# Memory.net
KiCad netlist of a schematic drawn in Altium Designer
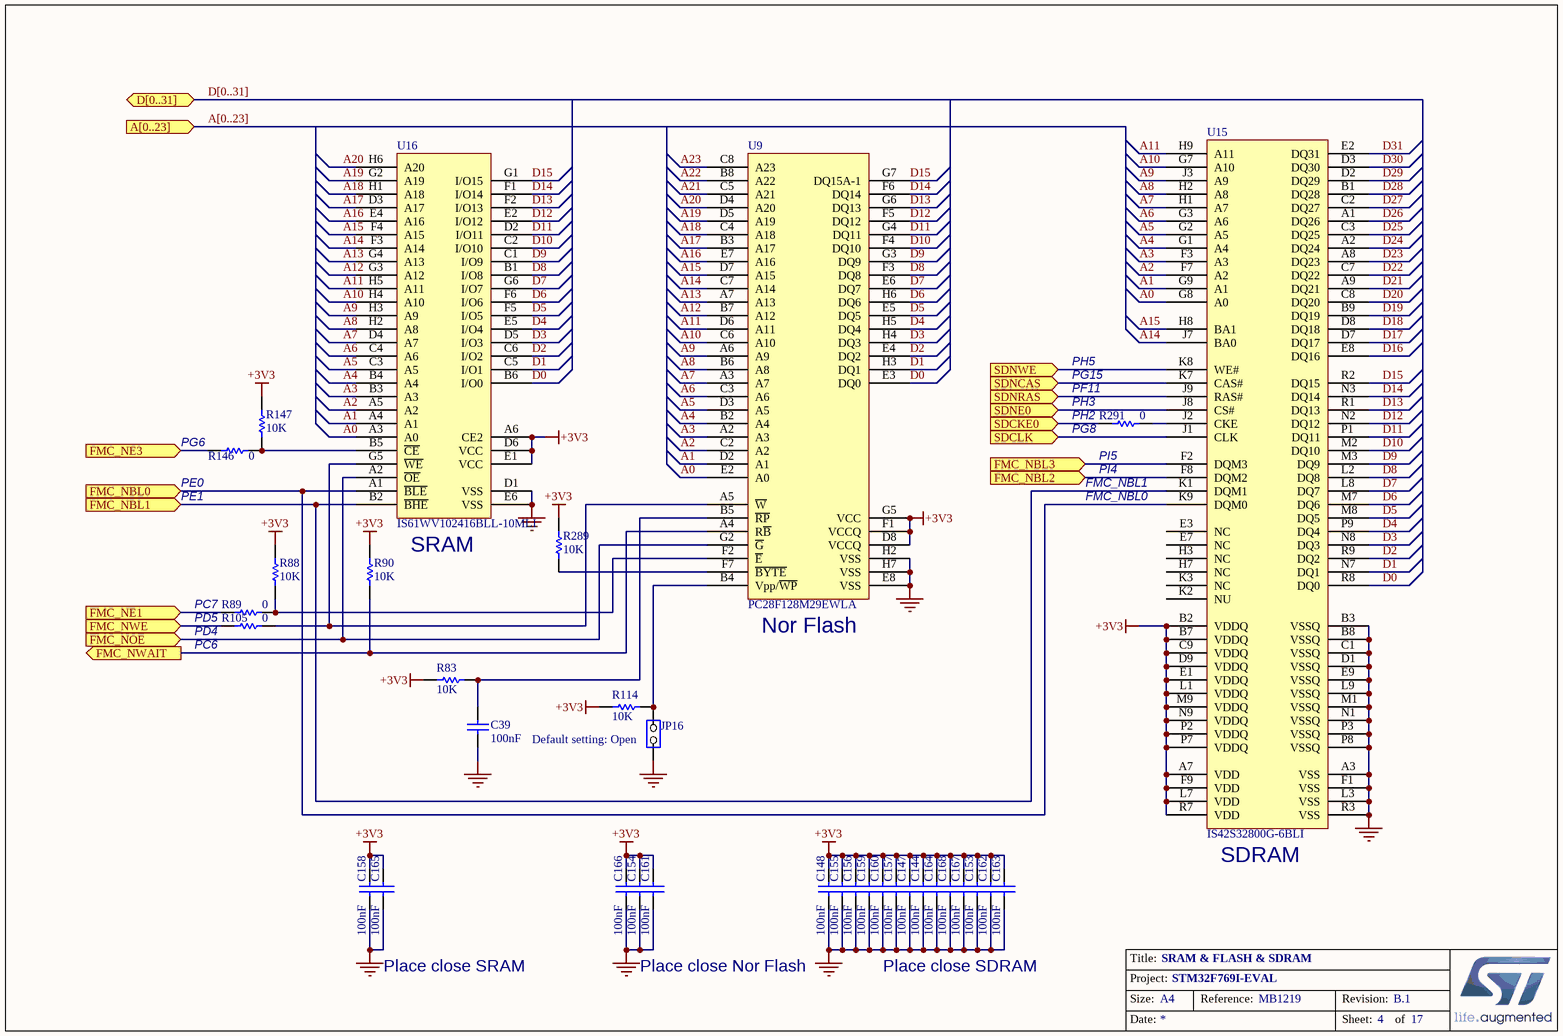
[diagram p0: Memory.SchDoc]

(export (version "E")
  (design (tool "Eeschema 10.0.6"))
  (components
    (comp (ref "C39")
      (value "100nF")
      (footprint "0603C")
      (description "Capacitor")
      (fields (field (name "PUBLISHER") "Altium Limited"))
      (libsource (lib "Miscellaneous Devices") (part "Cap"))
    )
    (comp (ref "C144")
      (value "100nF")
      (footprint "0603C")
      (description "Capacitor")
      (fields (field (name "PUBLISHER") "Altium Limited"))
      (libsource (lib "Miscellaneous Devices") (part "Cap"))
    )
    (comp (ref "C147")
      (value "100nF")
      (footprint "0603C")
      (description "Capacitor")
      (fields (field (name "PUBLISHER") "Altium Limited"))
      (libsource (lib "Miscellaneous Devices") (part "Cap"))
    )
    (comp (ref "C148")
      (value "100nF")
      (footprint "0603C")
      (description "Capacitor")
      (fields (field (name "PUBLISHER") "Altium Limited"))
      (libsource (lib "Miscellaneous Devices") (part "Cap"))
    )
    (comp (ref "C153")
      (value "100nF")
      (footprint "0603C")
      (description "Capacitor")
      (fields (field (name "PUBLISHER") "Altium Limited"))
      (libsource (lib "Miscellaneous Devices") (part "Cap"))
    )
    (comp (ref "C154")
      (value "100nF")
      (footprint "0603C")
      (description "Capacitor")
      (fields (field (name "PUBLISHER") "Altium Limited"))
      (libsource (lib "Miscellaneous Devices") (part "Cap"))
    )
    (comp (ref "C155")
      (value "100nF")
      (footprint "0603C")
      (description "Capacitor")
      (fields (field (name "PUBLISHER") "Altium Limited"))
      (libsource (lib "Miscellaneous Devices") (part "Cap"))
    )
    (comp (ref "C156")
      (value "100nF")
      (footprint "0603C")
      (description "Capacitor")
      (fields (field (name "PUBLISHER") "Altium Limited"))
      (libsource (lib "Miscellaneous Devices") (part "Cap"))
    )
    (comp (ref "C157")
      (value "100nF")
      (footprint "0603C")
      (description "Capacitor")
      (fields (field (name "PUBLISHER") "Altium Limited"))
      (libsource (lib "Miscellaneous Devices") (part "Cap"))
    )
    (comp (ref "C158")
      (value "100nF")
      (footprint "0603C")
      (description "Capacitor")
      (fields (field (name "PUBLISHER") "Altium Limited"))
      (libsource (lib "Miscellaneous Devices") (part "Cap"))
    )
    (comp (ref "C159")
      (value "100nF")
      (footprint "0603C")
      (description "Capacitor")
      (fields (field (name "PUBLISHER") "Altium Limited"))
      (libsource (lib "Miscellaneous Devices") (part "Cap"))
    )
    (comp (ref "C160")
      (value "100nF")
      (footprint "0603C")
      (description "Capacitor")
      (fields (field (name "PUBLISHER") "Altium Limited"))
      (libsource (lib "Miscellaneous Devices") (part "Cap"))
    )
    (comp (ref "C161")
      (value "100nF")
      (footprint "0603C")
      (description "Capacitor")
      (fields (field (name "PUBLISHER") "Altium Limited"))
      (libsource (lib "Miscellaneous Devices") (part "Cap"))
    )
    (comp (ref "C162")
      (value "100nF")
      (footprint "0603C")
      (description "Capacitor")
      (fields (field (name "PUBLISHER") "Altium Limited"))
      (libsource (lib "Miscellaneous Devices") (part "Cap"))
    )
    (comp (ref "C163")
      (value "100nF")
      (footprint "0603C")
      (description "Capacitor")
      (fields (field (name "PUBLISHER") "Altium Limited"))
      (libsource (lib "Miscellaneous Devices") (part "Cap"))
    )
    (comp (ref "C164")
      (value "100nF")
      (footprint "0603C")
      (description "Capacitor")
      (fields (field (name "PUBLISHER") "Altium Limited"))
      (libsource (lib "Miscellaneous Devices") (part "Cap"))
    )
    (comp (ref "C165")
      (value "100nF")
      (footprint "0603C")
      (description "Capacitor")
      (fields (field (name "PUBLISHER") "Altium Limited"))
      (libsource (lib "Miscellaneous Devices") (part "Cap"))
    )
    (comp (ref "C166")
      (value "100nF")
      (footprint "0603C")
      (description "Capacitor")
      (fields (field (name "PUBLISHER") "Altium Limited"))
      (libsource (lib "Miscellaneous Devices") (part "Cap"))
    )
    (comp (ref "C167")
      (value "100nF")
      (footprint "0603C")
      (description "Capacitor")
      (fields (field (name "PUBLISHER") "Altium Limited"))
      (libsource (lib "Miscellaneous Devices") (part "Cap"))
    )
    (comp (ref "C168")
      (value "100nF")
      (footprint "0603C")
      (description "Capacitor")
      (fields (field (name "PUBLISHER") "Altium Limited"))
      (libsource (lib "Miscellaneous Devices") (part "Cap"))
    )
    (comp (ref "JP16") (value "~") (footprint "SIP2") (libsource (lib "*") (part "JP2")))
    (comp (ref "R83")
      (value "10K")
      (footprint "0603R")
      (description "Resistor")
      (fields (field (name "PUBLISHER") "Altium Limited"))
      (libsource (lib "Miscellaneous Devices") (part "Res1"))
    )
    (comp (ref "R88")
      (value "10K")
      (footprint "0603R")
      (description "Resistor")
      (fields (field (name "PUBLISHER") "Altium Limited"))
      (libsource (lib "Miscellaneous Devices") (part "Res1"))
    )
    (comp (ref "R89")
      (value "0")
      (footprint "0603R")
      (description "Resistor")
      (fields (field (name "PUBLISHER") "Altium Limited"))
      (libsource (lib "Miscellaneous Devices") (part "Res1"))
    )
    (comp (ref "R90")
      (value "10K")
      (footprint "0603R")
      (description "Resistor")
      (fields (field (name "PUBLISHER") "Altium Limited"))
      (libsource (lib "Miscellaneous Devices") (part "Res1"))
    )
    (comp (ref "R105")
      (value "0")
      (footprint "0603R")
      (description "Resistor")
      (fields (field (name "PUBLISHER") "Altium Limited"))
      (libsource (lib "Miscellaneous Devices") (part "Res1"))
    )
    (comp (ref "R114")
      (value "10K")
      (footprint "0603R")
      (description "Resistor")
      (fields (field (name "PUBLISHER") "Altium Limited"))
      (libsource (lib "Miscellaneous Devices") (part "Res1"))
    )
    (comp (ref "R146")
      (value "0")
      (footprint "0603R")
      (description "Resistor")
      (fields (field (name "PUBLISHER") "Altium Limited"))
      (libsource (lib "Miscellaneous Devices") (part "Res1"))
    )
    (comp (ref "R147")
      (value "10K")
      (footprint "0603R")
      (description "Resistor")
      (fields (field (name "PUBLISHER") "Altium Limited"))
      (libsource (lib "Miscellaneous Devices") (part "Res1"))
    )
    (comp (ref "R289")
      (value "10K")
      (footprint "0603R")
      (description "Resistor")
      (fields (field (name "PUBLISHER") "Altium Limited"))
      (libsource (lib "Miscellaneous Devices") (part "Res1"))
    )
    (comp (ref "R291")
      (value "0")
      (footprint "0603R")
      (description "Resistor")
      (fields (field (name "PUBLISHER") "Altium Limited"))
      (libsource (lib "Miscellaneous Devices") (part "Res1"))
    )
    (comp (ref "U9")
      (value "PC28F128M29EWLA")
      (footprint "FBGA64_1_11X13")
      (libsource (lib "MB964") (part "M29W128FL70ZA6E"))
    )
    (comp (ref "U15")
      (value "IS42S32800G-6BLI")
      (footprint "FBGA90_0R8_8X13")
      (libsource (lib "mb1045") (part "MT48LC4M32B2B5"))
    )
    (comp (ref "U16")
      (value "IS61WV102416BLL-10MLI")
      (footprint "BGA48_0R75_9X11")
      (libsource (lib "MB901") (part "IS61WV102416BLL-10MLI"))
    )
  )
  (nets
    (net (code "1") (name "+3V3") (class "Default")
      (node (ref "C144") (pin "1") (pinfunction "1_1") (pintype "passive"))
      (node (ref "C147") (pin "1") (pinfunction "1_1") (pintype "passive"))
      (node (ref "C148") (pin "1") (pinfunction "1_1") (pintype "passive"))
      (node (ref "C153") (pin "1") (pinfunction "1_1") (pintype "passive"))
      (node (ref "C154") (pin "1") (pinfunction "1_1") (pintype "passive"))
      (node (ref "C155") (pin "1") (pinfunction "1_1") (pintype "passive"))
      (node (ref "C156") (pin "1") (pinfunction "1_1") (pintype "passive"))
      (node (ref "C157") (pin "1") (pinfunction "1_1") (pintype "passive"))
      (node (ref "C158") (pin "1") (pinfunction "1_1") (pintype "passive"))
      (node (ref "C159") (pin "1") (pinfunction "1_1") (pintype "passive"))
      (node (ref "C160") (pin "1") (pinfunction "1_1") (pintype "passive"))
      (node (ref "C161") (pin "1") (pinfunction "1_1") (pintype "passive"))
      (node (ref "C162") (pin "1") (pinfunction "1_1") (pintype "passive"))
      (node (ref "C163") (pin "1") (pinfunction "1_1") (pintype "passive"))
      (node (ref "C164") (pin "1") (pinfunction "1_1") (pintype "passive"))
      (node (ref "C165") (pin "1") (pinfunction "1_1") (pintype "passive"))
      (node (ref "C166") (pin "1") (pinfunction "1_1") (pintype "passive"))
      (node (ref "C167") (pin "1") (pinfunction "1_1") (pintype "passive"))
      (node (ref "C168") (pin "1") (pinfunction "1_1") (pintype "passive"))
      (node (ref "R114") (pin "2") (pinfunction "2_2") (pintype "passive"))
      (node (ref "R147") (pin "2") (pinfunction "2_2") (pintype "passive"))
      (node (ref "R289") (pin "2") (pinfunction "2_2") (pintype "passive"))
      (node (ref "R83") (pin "1") (pinfunction "1_1") (pintype "passive"))
      (node (ref "R88") (pin "2") (pinfunction "2_2") (pintype "passive"))
      (node (ref "R90") (pin "2") (pinfunction "2_2") (pintype "passive"))
      (node (ref "U15") (pin "A7") (pinfunction "VDD_A7") (pintype "passive"))
      (node (ref "U15") (pin "B2") (pinfunction "VDDQ_B2") (pintype "passive"))
      (node (ref "U15") (pin "B7") (pinfunction "VDDQ_B7") (pintype "passive"))
      (node (ref "U15") (pin "C9") (pinfunction "VDDQ_C9") (pintype "passive"))
      (node (ref "U15") (pin "D9") (pinfunction "VDDQ_D9") (pintype "passive"))
      (node (ref "U15") (pin "E1") (pinfunction "VDDQ_E1") (pintype "passive"))
      (node (ref "U15") (pin "F9") (pinfunction "VDD_F9") (pintype "passive"))
      (node (ref "U15") (pin "L1") (pinfunction "VDDQ_L1") (pintype "passive"))
      (node (ref "U15") (pin "L7") (pinfunction "VDD_L7") (pintype "passive"))
      (node (ref "U15") (pin "M9") (pinfunction "VDDQ_M9") (pintype "passive"))
      (node (ref "U15") (pin "N9") (pinfunction "VDDQ_N9") (pintype "passive"))
      (node (ref "U15") (pin "P2") (pinfunction "VDDQ_P2") (pintype "passive"))
      (node (ref "U15") (pin "P7") (pinfunction "VDDQ_P7") (pintype "passive"))
      (node (ref "U15") (pin "R7") (pinfunction "VDD_R7") (pintype "passive"))
      (node (ref "U16") (pin "A6") (pinfunction "CE2_A6") (pintype "passive"))
      (node (ref "U16") (pin "D6") (pinfunction "VCC_D6") (pintype "passive"))
      (node (ref "U16") (pin "E1") (pinfunction "VCC_E1") (pintype "passive"))
      (node (ref "U9") (pin "D8") (pinfunction "VCCQ_D8") (pintype "passive"))
      (node (ref "U9") (pin "F1") (pinfunction "VCCQ_F1") (pintype "passive"))
      (node (ref "U9") (pin "G5") (pinfunction "VCC_G5") (pintype "passive"))
    )
    (net (code "2") (name "/A0") (class "Default")
      (node (ref "U15") (pin "G8") (pinfunction "A0_G8") (pintype "passive"))
      (node (ref "U16") (pin "A3") (pinfunction "A0_A3") (pintype "passive"))
      (node (ref "U9") (pin "E2") (pinfunction "A0_E2") (pintype "passive"))
    )
    (net (code "3") (name "/A1") (class "Default")
      (node (ref "U15") (pin "G9") (pinfunction "A1_G9") (pintype "passive"))
      (node (ref "U16") (pin "A4") (pinfunction "A1_A4") (pintype "passive"))
      (node (ref "U9") (pin "D2") (pinfunction "A1_D2") (pintype "passive"))
    )
    (net (code "4") (name "/A2") (class "Default")
      (node (ref "U15") (pin "F7") (pinfunction "A2_F7") (pintype "passive"))
      (node (ref "U16") (pin "A5") (pinfunction "A2_A5") (pintype "passive"))
      (node (ref "U9") (pin "C2") (pinfunction "A2_C2") (pintype "passive"))
    )
    (net (code "5") (name "/A3") (class "Default")
      (node (ref "U15") (pin "F3") (pinfunction "A3_F3") (pintype "passive"))
      (node (ref "U16") (pin "B3") (pinfunction "A3_B3") (pintype "passive"))
      (node (ref "U9") (pin "A2") (pinfunction "A3_A2") (pintype "passive"))
    )
    (net (code "6") (name "/A4") (class "Default")
      (node (ref "U15") (pin "G1") (pinfunction "A4_G1") (pintype "passive"))
      (node (ref "U16") (pin "B4") (pinfunction "A4_B4") (pintype "passive"))
      (node (ref "U9") (pin "B2") (pinfunction "A4_B2") (pintype "passive"))
    )
    (net (code "7") (name "/A5") (class "Default")
      (node (ref "U15") (pin "G2") (pinfunction "A5_G2") (pintype "passive"))
      (node (ref "U16") (pin "C3") (pinfunction "A5_C3") (pintype "passive"))
      (node (ref "U9") (pin "D3") (pinfunction "A5_D3") (pintype "passive"))
    )
    (net (code "8") (name "/A6") (class "Default")
      (node (ref "U15") (pin "G3") (pinfunction "A6_G3") (pintype "passive"))
      (node (ref "U16") (pin "C4") (pinfunction "A6_C4") (pintype "passive"))
      (node (ref "U9") (pin "C3") (pinfunction "A6_C3") (pintype "passive"))
    )
    (net (code "9") (name "/A7") (class "Default")
      (node (ref "U15") (pin "H1") (pinfunction "A7_H1") (pintype "passive"))
      (node (ref "U16") (pin "D4") (pinfunction "A7_D4") (pintype "passive"))
      (node (ref "U9") (pin "A3") (pinfunction "A7_A3") (pintype "passive"))
    )
    (net (code "10") (name "/A8") (class "Default")
      (node (ref "U15") (pin "H2") (pinfunction "A8_H2") (pintype "passive"))
      (node (ref "U16") (pin "H2") (pinfunction "A8_H2") (pintype "passive"))
      (node (ref "U9") (pin "B6") (pinfunction "A8_B6") (pintype "passive"))
    )
    (net (code "11") (name "/A9") (class "Default")
      (node (ref "U15") (pin "J3") (pinfunction "A9_J3") (pintype "passive"))
      (node (ref "U16") (pin "H3") (pinfunction "A9_H3") (pintype "passive"))
      (node (ref "U9") (pin "A6") (pinfunction "A9_A6") (pintype "passive"))
    )
    (net (code "12") (name "/A10") (class "Default")
      (node (ref "U15") (pin "G7") (pinfunction "A10_G7") (pintype "passive"))
      (node (ref "U16") (pin "H4") (pinfunction "A10_H4") (pintype "passive"))
      (node (ref "U9") (pin "C6") (pinfunction "A10_C6") (pintype "passive"))
    )
    (net (code "13") (name "/A11") (class "Default")
      (node (ref "U15") (pin "H9") (pinfunction "A11_H9") (pintype "passive"))
      (node (ref "U16") (pin "H5") (pinfunction "A11_H5") (pintype "passive"))
      (node (ref "U9") (pin "D6") (pinfunction "A11_D6") (pintype "passive"))
    )
    (net (code "14") (name "/A12") (class "Default")
      (node (ref "U16") (pin "G3") (pinfunction "A12_G3") (pintype "passive"))
      (node (ref "U9") (pin "B7") (pinfunction "A12_B7") (pintype "passive"))
    )
    (net (code "15") (name "/A13") (class "Default")
      (node (ref "U16") (pin "G4") (pinfunction "A13_G4") (pintype "passive"))
      (node (ref "U9") (pin "A7") (pinfunction "A13_A7") (pintype "passive"))
    )
    (net (code "16") (name "/A14") (class "Default")
      (node (ref "U15") (pin "J7") (pinfunction "BA0_J7") (pintype "passive"))
      (node (ref "U16") (pin "F3") (pinfunction "A14_F3") (pintype "passive"))
      (node (ref "U9") (pin "C7") (pinfunction "A14_C7") (pintype "passive"))
    )
    (net (code "17") (name "/A15") (class "Default")
      (node (ref "U15") (pin "H8") (pinfunction "BA1_H8") (pintype "passive"))
      (node (ref "U16") (pin "F4") (pinfunction "A15_F4") (pintype "passive"))
      (node (ref "U9") (pin "D7") (pinfunction "A15_D7") (pintype "passive"))
    )
    (net (code "18") (name "/A16") (class "Default")
      (node (ref "U16") (pin "E4") (pinfunction "A16_E4") (pintype "passive"))
      (node (ref "U9") (pin "E7") (pinfunction "A16_E7") (pintype "passive"))
    )
    (net (code "19") (name "/A17") (class "Default")
      (node (ref "U16") (pin "D3") (pinfunction "A17_D3") (pintype "passive"))
      (node (ref "U9") (pin "B3") (pinfunction "A17_B3") (pintype "passive"))
    )
    (net (code "20") (name "/A18") (class "Default")
      (node (ref "U16") (pin "H1") (pinfunction "A18_H1") (pintype "passive"))
      (node (ref "U9") (pin "C4") (pinfunction "A18_C4") (pintype "passive"))
    )
    (net (code "21") (name "/A19") (class "Default")
      (node (ref "U16") (pin "G2") (pinfunction "A19_G2") (pintype "passive"))
      (node (ref "U9") (pin "D5") (pinfunction "A19_D5") (pintype "passive"))
    )
    (net (code "22") (name "/A20") (class "Default")
      (node (ref "U16") (pin "H6") (pinfunction "A20_H6") (pintype "passive"))
      (node (ref "U9") (pin "D4") (pinfunction "A20_D4") (pintype "passive"))
    )
    (net (code "23") (name "/A21") (class "Default")
      (node (ref "U9") (pin "C5") (pinfunction "A21_C5") (pintype "passive"))
    )
    (net (code "24") (name "/A22") (class "Default")
      (node (ref "U9") (pin "B8") (pinfunction "A22_B8") (pintype "passive"))
    )
    (net (code "25") (name "/A23") (class "Default")
      (node (ref "U9") (pin "C8") (pinfunction "A23_C8") (pintype "passive"))
    )
    (net (code "27") (name "/D0") (class "Default")
      (node (ref "U15") (pin "R8") (pinfunction "DQ0_R8") (pintype "passive"))
      (node (ref "U16") (pin "B6") (pinfunction "I/O0_B6") (pintype "passive"))
      (node (ref "U9") (pin "E3") (pinfunction "DQ0_E3") (pintype "passive"))
    )
    (net (code "28") (name "/D1") (class "Default")
      (node (ref "U15") (pin "N7") (pinfunction "DQ1_N7") (pintype "passive"))
      (node (ref "U16") (pin "C5") (pinfunction "I/O1_C5") (pintype "passive"))
      (node (ref "U9") (pin "H3") (pinfunction "DQ1_H3") (pintype "passive"))
    )
    (net (code "29") (name "/D2") (class "Default")
      (node (ref "U15") (pin "R9") (pinfunction "DQ2_R9") (pintype "passive"))
      (node (ref "U16") (pin "C6") (pinfunction "I/O2_C6") (pintype "passive"))
      (node (ref "U9") (pin "E4") (pinfunction "DQ2_E4") (pintype "passive"))
    )
    (net (code "30") (name "/D3") (class "Default")
      (node (ref "U15") (pin "N8") (pinfunction "DQ3_N8") (pintype "passive"))
      (node (ref "U16") (pin "D5") (pinfunction "I/O3_D5") (pintype "passive"))
      (node (ref "U9") (pin "H4") (pinfunction "DQ3_H4") (pintype "passive"))
    )
    (net (code "31") (name "/D4") (class "Default")
      (node (ref "U15") (pin "P9") (pinfunction "DQ4_P9") (pintype "passive"))
      (node (ref "U16") (pin "E5") (pinfunction "I/O4_E5") (pintype "passive"))
      (node (ref "U9") (pin "H5") (pinfunction "DQ4_H5") (pintype "passive"))
    )
    (net (code "32") (name "/D5") (class "Default")
      (node (ref "U15") (pin "M8") (pinfunction "DQ5_M8") (pintype "passive"))
      (node (ref "U16") (pin "F5") (pinfunction "I/O5_F5") (pintype "passive"))
      (node (ref "U9") (pin "E5") (pinfunction "DQ5_E5") (pintype "passive"))
    )
    (net (code "33") (name "/D6") (class "Default")
      (node (ref "U15") (pin "M7") (pinfunction "DQ6_M7") (pintype "passive"))
      (node (ref "U16") (pin "F6") (pinfunction "I/O6_F6") (pintype "passive"))
      (node (ref "U9") (pin "H6") (pinfunction "DQ6_H6") (pintype "passive"))
    )
    (net (code "34") (name "/D7") (class "Default")
      (node (ref "U15") (pin "L8") (pinfunction "DQ7_L8") (pintype "passive"))
      (node (ref "U16") (pin "G6") (pinfunction "I/O7_G6") (pintype "passive"))
      (node (ref "U9") (pin "E6") (pinfunction "DQ7_E6") (pintype "passive"))
    )
    (net (code "35") (name "/D8") (class "Default")
      (node (ref "U15") (pin "L2") (pinfunction "DQ8_L2") (pintype "passive"))
      (node (ref "U16") (pin "B1") (pinfunction "I/O8_B1") (pintype "passive"))
      (node (ref "U9") (pin "F3") (pinfunction "DQ8_F3") (pintype "passive"))
    )
    (net (code "36") (name "/D9") (class "Default")
      (node (ref "U15") (pin "M3") (pinfunction "DQ9_M3") (pintype "passive"))
      (node (ref "U16") (pin "C1") (pinfunction "I/O9_C1") (pintype "passive"))
      (node (ref "U9") (pin "G3") (pinfunction "DQ9_G3") (pintype "passive"))
    )
    (net (code "37") (name "/D10") (class "Default")
      (node (ref "U15") (pin "M2") (pinfunction "DQ10_M2") (pintype "passive"))
      (node (ref "U16") (pin "C2") (pinfunction "I/O10_C2") (pintype "passive"))
      (node (ref "U9") (pin "F4") (pinfunction "DQ10_F4") (pintype "passive"))
    )
    (net (code "38") (name "/D11") (class "Default")
      (node (ref "U15") (pin "P1") (pinfunction "DQ11_P1") (pintype "passive"))
      (node (ref "U16") (pin "D2") (pinfunction "I/O11_D2") (pintype "passive"))
      (node (ref "U9") (pin "G4") (pinfunction "DQ11_G4") (pintype "passive"))
    )
    (net (code "39") (name "/D12") (class "Default")
      (node (ref "U15") (pin "N2") (pinfunction "DQ12_N2") (pintype "passive"))
      (node (ref "U16") (pin "E2") (pinfunction "I/O12_E2") (pintype "passive"))
      (node (ref "U9") (pin "F5") (pinfunction "DQ12_F5") (pintype "passive"))
    )
    (net (code "40") (name "/D13") (class "Default")
      (node (ref "U15") (pin "R1") (pinfunction "DQ13_R1") (pintype "passive"))
      (node (ref "U16") (pin "F2") (pinfunction "I/O13_F2") (pintype "passive"))
      (node (ref "U9") (pin "G6") (pinfunction "DQ13_G6") (pintype "passive"))
    )
    (net (code "41") (name "/D14") (class "Default")
      (node (ref "U15") (pin "N3") (pinfunction "DQ14_N3") (pintype "passive"))
      (node (ref "U16") (pin "F1") (pinfunction "I/O14_F1") (pintype "passive"))
      (node (ref "U9") (pin "F6") (pinfunction "DQ14_F6") (pintype "passive"))
    )
    (net (code "42") (name "/D15") (class "Default")
      (node (ref "U15") (pin "R2") (pinfunction "DQ15_R2") (pintype "passive"))
      (node (ref "U16") (pin "G1") (pinfunction "I/O15_G1") (pintype "passive"))
      (node (ref "U9") (pin "G7") (pinfunction "DQ15A-1_G7") (pintype "passive"))
    )
    (net (code "43") (name "/D16") (class "Default")
      (node (ref "U15") (pin "E8") (pinfunction "DQ16_E8") (pintype "passive"))
    )
    (net (code "44") (name "/D17") (class "Default")
      (node (ref "U15") (pin "D7") (pinfunction "DQ17_D7") (pintype "passive"))
    )
    (net (code "45") (name "/D18") (class "Default")
      (node (ref "U15") (pin "D8") (pinfunction "DQ18_D8") (pintype "passive"))
    )
    (net (code "46") (name "/D19") (class "Default")
      (node (ref "U15") (pin "B9") (pinfunction "DQ19_B9") (pintype "passive"))
    )
    (net (code "47") (name "/D20") (class "Default")
      (node (ref "U15") (pin "C8") (pinfunction "DQ20_C8") (pintype "passive"))
    )
    (net (code "48") (name "/D21") (class "Default")
      (node (ref "U15") (pin "A9") (pinfunction "DQ21_A9") (pintype "passive"))
    )
    (net (code "49") (name "/D22") (class "Default")
      (node (ref "U15") (pin "C7") (pinfunction "DQ22_C7") (pintype "passive"))
    )
    (net (code "50") (name "/D23") (class "Default")
      (node (ref "U15") (pin "A8") (pinfunction "DQ23_A8") (pintype "passive"))
    )
    (net (code "51") (name "/D24") (class "Default")
      (node (ref "U15") (pin "A2") (pinfunction "DQ24_A2") (pintype "passive"))
    )
    (net (code "52") (name "/D25") (class "Default")
      (node (ref "U15") (pin "C3") (pinfunction "DQ25_C3") (pintype "passive"))
    )
    (net (code "53") (name "/D26") (class "Default")
      (node (ref "U15") (pin "A1") (pinfunction "DQ26_A1") (pintype "passive"))
    )
    (net (code "54") (name "/D27") (class "Default")
      (node (ref "U15") (pin "C2") (pinfunction "DQ27_C2") (pintype "passive"))
    )
    (net (code "55") (name "/D28") (class "Default")
      (node (ref "U15") (pin "B1") (pinfunction "DQ28_B1") (pintype "passive"))
    )
    (net (code "56") (name "/D29") (class "Default")
      (node (ref "U15") (pin "D2") (pinfunction "DQ29_D2") (pintype "passive"))
    )
    (net (code "57") (name "/D30") (class "Default")
      (node (ref "U15") (pin "D3") (pinfunction "DQ30_D3") (pintype "passive"))
    )
    (net (code "58") (name "/D31") (class "Default")
      (node (ref "U15") (pin "E2") (pinfunction "DQ31_E2") (pintype "passive"))
    )
    (net (code "60") (name "/FMC_NBL0") (class "Default")
      (node (ref "U15") (pin "K9") (pinfunction "DQM0_K9") (pintype "passive"))
      (node (ref "U16") (pin "A1") (pinfunction "~{BLE}_A1") (pintype "passive"))
    )
    (net (code "61") (name "/FMC_NBL1") (class "Default")
      (node (ref "U15") (pin "K1") (pinfunction "DQM1_K1") (pintype "passive"))
      (node (ref "U16") (pin "B2") (pinfunction "~{BHE}_B2") (pintype "passive"))
    )
    (net (code "62") (name "/FMC_NBL2") (class "Default")
      (node (ref "U15") (pin "F8") (pinfunction "DQM2_F8") (pintype "passive"))
    )
    (net (code "63") (name "/FMC_NBL3") (class "Default")
      (node (ref "U15") (pin "F2") (pinfunction "DQM3_F2") (pintype "passive"))
    )
    (net (code "64") (name "/FMC_NE1") (class "Default")
      (node (ref "R89") (pin "2") (pinfunction "2_2") (pintype "passive"))
    )
    (net (code "65") (name "/FMC_NE3") (class "Default")
      (node (ref "R146") (pin "2") (pinfunction "2_2") (pintype "passive"))
    )
    (net (code "66") (name "/FMC_NOE") (class "Default")
      (node (ref "U16") (pin "A2") (pinfunction "~{OE}_A2") (pintype "passive"))
      (node (ref "U9") (pin "G2") (pinfunction "~{G}_G2") (pintype "passive"))
    )
    (net (code "67") (name "/FMC_NWAIT") (class "Default")
      (node (ref "R90") (pin "1") (pinfunction "1_1") (pintype "passive"))
      (node (ref "U9") (pin "A4") (pinfunction "R~{B}_A4") (pintype "passive"))
    )
    (net (code "68") (name "/FMC_NWE") (class "Default")
      (node (ref "R105") (pin "2") (pinfunction "2_2") (pintype "passive"))
    )
    (net (code "69") (name "/SDCKE0") (class "Default")
      (node (ref "R291") (pin "2") (pinfunction "2_2") (pintype "passive"))
    )
    (net (code "70") (name "/SDCLK") (class "Default")
      (node (ref "U15") (pin "J1") (pinfunction "CLK_J1") (pintype "passive"))
    )
    (net (code "71") (name "/SDNCAS") (class "Default")
      (node (ref "U15") (pin "K7") (pinfunction "CAS#_K7") (pintype "passive"))
    )
    (net (code "72") (name "/SDNE0") (class "Default")
      (node (ref "U15") (pin "J8") (pinfunction "CS#_J8") (pintype "passive"))
    )
    (net (code "73") (name "/SDNRAS") (class "Default")
      (node (ref "U15") (pin "J9") (pinfunction "RAS#_J9") (pintype "passive"))
    )
    (net (code "74") (name "/SDNWE") (class "Default")
      (node (ref "U15") (pin "K8") (pinfunction "WE#_K8") (pintype "passive"))
    )
    (net (code "75") (name "GND") (class "Default")
      (node (ref "C144") (pin "2") (pinfunction "2_2") (pintype "passive"))
      (node (ref "C147") (pin "2") (pinfunction "2_2") (pintype "passive"))
      (node (ref "C148") (pin "2") (pinfunction "2_2") (pintype "passive"))
      (node (ref "C153") (pin "2") (pinfunction "2_2") (pintype "passive"))
      (node (ref "C154") (pin "2") (pinfunction "2_2") (pintype "passive"))
      (node (ref "C155") (pin "2") (pinfunction "2_2") (pintype "passive"))
      (node (ref "C156") (pin "2") (pinfunction "2_2") (pintype "passive"))
      (node (ref "C157") (pin "2") (pinfunction "2_2") (pintype "passive"))
      (node (ref "C158") (pin "2") (pinfunction "2_2") (pintype "passive"))
      (node (ref "C159") (pin "2") (pinfunction "2_2") (pintype "passive"))
      (node (ref "C160") (pin "2") (pinfunction "2_2") (pintype "passive"))
      (node (ref "C161") (pin "2") (pinfunction "2_2") (pintype "passive"))
      (node (ref "C162") (pin "2") (pinfunction "2_2") (pintype "passive"))
      (node (ref "C163") (pin "2") (pinfunction "2_2") (pintype "passive"))
      (node (ref "C164") (pin "2") (pinfunction "2_2") (pintype "passive"))
      (node (ref "C165") (pin "2") (pinfunction "2_2") (pintype "passive"))
      (node (ref "C166") (pin "2") (pinfunction "2_2") (pintype "passive"))
      (node (ref "C167") (pin "2") (pinfunction "2_2") (pintype "passive"))
      (node (ref "C168") (pin "2") (pinfunction "2_2") (pintype "passive"))
      (node (ref "C39") (pin "2") (pinfunction "2_2") (pintype "passive"))
      (node (ref "JP16") (pin "1") (pinfunction "COMMON_1") (pintype "passive"))
      (node (ref "U15") (pin "A3") (pinfunction "VSS_A3") (pintype "passive"))
      (node (ref "U15") (pin "B3") (pinfunction "VSSQ_B3") (pintype "passive"))
      (node (ref "U15") (pin "B8") (pinfunction "VSSQ_B8") (pintype "passive"))
      (node (ref "U15") (pin "C1") (pinfunction "VSSQ_C1") (pintype "passive"))
      (node (ref "U15") (pin "D1") (pinfunction "VSSQ_D1") (pintype "passive"))
      (node (ref "U15") (pin "E9") (pinfunction "VSSQ_E9") (pintype "passive"))
      (node (ref "U15") (pin "F1") (pinfunction "VSS_F1") (pintype "passive"))
      (node (ref "U15") (pin "L3") (pinfunction "VSS_L3") (pintype "passive"))
      (node (ref "U15") (pin "L9") (pinfunction "VSSQ_L9") (pintype "passive"))
      (node (ref "U15") (pin "M1") (pinfunction "VSSQ_M1") (pintype "passive"))
      (node (ref "U15") (pin "N1") (pinfunction "VSSQ_N1") (pintype "passive"))
      (node (ref "U15") (pin "P3") (pinfunction "VSSQ_P3") (pintype "passive"))
      (node (ref "U15") (pin "P8") (pinfunction "VSSQ_P8") (pintype "passive"))
      (node (ref "U15") (pin "R3") (pinfunction "VSS_R3") (pintype "passive"))
      (node (ref "U16") (pin "D1") (pinfunction "VSS_D1") (pintype "passive"))
      (node (ref "U16") (pin "E6") (pinfunction "VSS_E6") (pintype "passive"))
      (node (ref "U9") (pin "E8") (pinfunction "VSS_E8") (pintype "passive"))
      (node (ref "U9") (pin "H2") (pinfunction "VSS_H2") (pintype "passive"))
      (node (ref "U9") (pin "H7") (pinfunction "VSS_H7") (pintype "passive"))
    )
    (net (code "76") (name "Net-(JP16-NO)") (class "Default")
      (node (ref "JP16") (pin "2") (pinfunction "NO_2") (pintype "passive"))
      (node (ref "R114") (pin "1") (pinfunction "1_1") (pintype "passive"))
      (node (ref "U9") (pin "B4") (pinfunction "Vpp/~{WP}_B4") (pintype "passive"))
    )
    (net (code "77") (name "Net-(U9-~{BYTE})") (class "Default")
      (node (ref "R289") (pin "1") (pinfunction "1_1") (pintype "passive"))
      (node (ref "U9") (pin "F7") (pinfunction "~{BYTE}_F7") (pintype "passive"))
    )
    (net (code "78") (name "Net-(U9-~{E})") (class "Default")
      (node (ref "R88") (pin "1") (pinfunction "1_1") (pintype "passive"))
      (node (ref "R89") (pin "1") (pinfunction "1_1") (pintype "passive"))
      (node (ref "U9") (pin "F2") (pinfunction "~{E}_F2") (pintype "passive"))
    )
    (net (code "79") (name "Net-(U9-~{RP})") (class "Default")
      (node (ref "C39") (pin "1") (pinfunction "1_1") (pintype "passive"))
      (node (ref "R83") (pin "2") (pinfunction "2_2") (pintype "passive"))
      (node (ref "U9") (pin "B5") (pinfunction "~{RP}_B5") (pintype "passive"))
    )
    (net (code "80") (name "Net-(U15-CKE)") (class "Default")
      (node (ref "R291") (pin "1") (pinfunction "1_1") (pintype "passive"))
      (node (ref "U15") (pin "J2") (pinfunction "CKE_J2") (pintype "passive"))
    )
    (net (code "81") (name "Net-(U16-~{CE})") (class "Default")
      (node (ref "R146") (pin "1") (pinfunction "1_1") (pintype "passive"))
      (node (ref "R147") (pin "1") (pinfunction "1_1") (pintype "passive"))
      (node (ref "U16") (pin "B5") (pinfunction "~{CE}_B5") (pintype "passive"))
    )
    (net (code "82") (name "Net-(U16-~{WE})") (class "Default")
      (node (ref "R105") (pin "1") (pinfunction "1_1") (pintype "passive"))
      (node (ref "U16") (pin "G5") (pinfunction "~{WE}_G5") (pintype "passive"))
      (node (ref "U9") (pin "A5") (pinfunction "~{W}_A5") (pintype "passive"))
    )
    (net (code "83") (name "unconnected-(U15-NC-PadE3)") (class "Default")
      (node (ref "U15") (pin "E3") (pinfunction "NC_E3") (pintype "passive"))
    )
    (net (code "84") (name "unconnected-(U15-NC-PadE7)") (class "Default")
      (node (ref "U15") (pin "E7") (pinfunction "NC_E7") (pintype "passive"))
    )
    (net (code "85") (name "unconnected-(U15-NC-PadH3)") (class "Default")
      (node (ref "U15") (pin "H3") (pinfunction "NC_H3") (pintype "passive"))
    )
    (net (code "86") (name "unconnected-(U15-NC-PadH7)") (class "Default")
      (node (ref "U15") (pin "H7") (pinfunction "NC_H7") (pintype "passive"))
    )
    (net (code "87") (name "unconnected-(U15-NC-PadK3)") (class "Default")
      (node (ref "U15") (pin "K3") (pinfunction "NC_K3") (pintype "passive"))
    )
    (net (code "88") (name "unconnected-(U15-NU-PadK2)") (class "Default")
      (node (ref "U15") (pin "K2") (pinfunction "NU_K2") (pintype "passive"))
    )
  )
)
